# Adafruit_555_PWM_Output_STEMMA.net
KiCad netlist of a schematic drawn in EAGLE
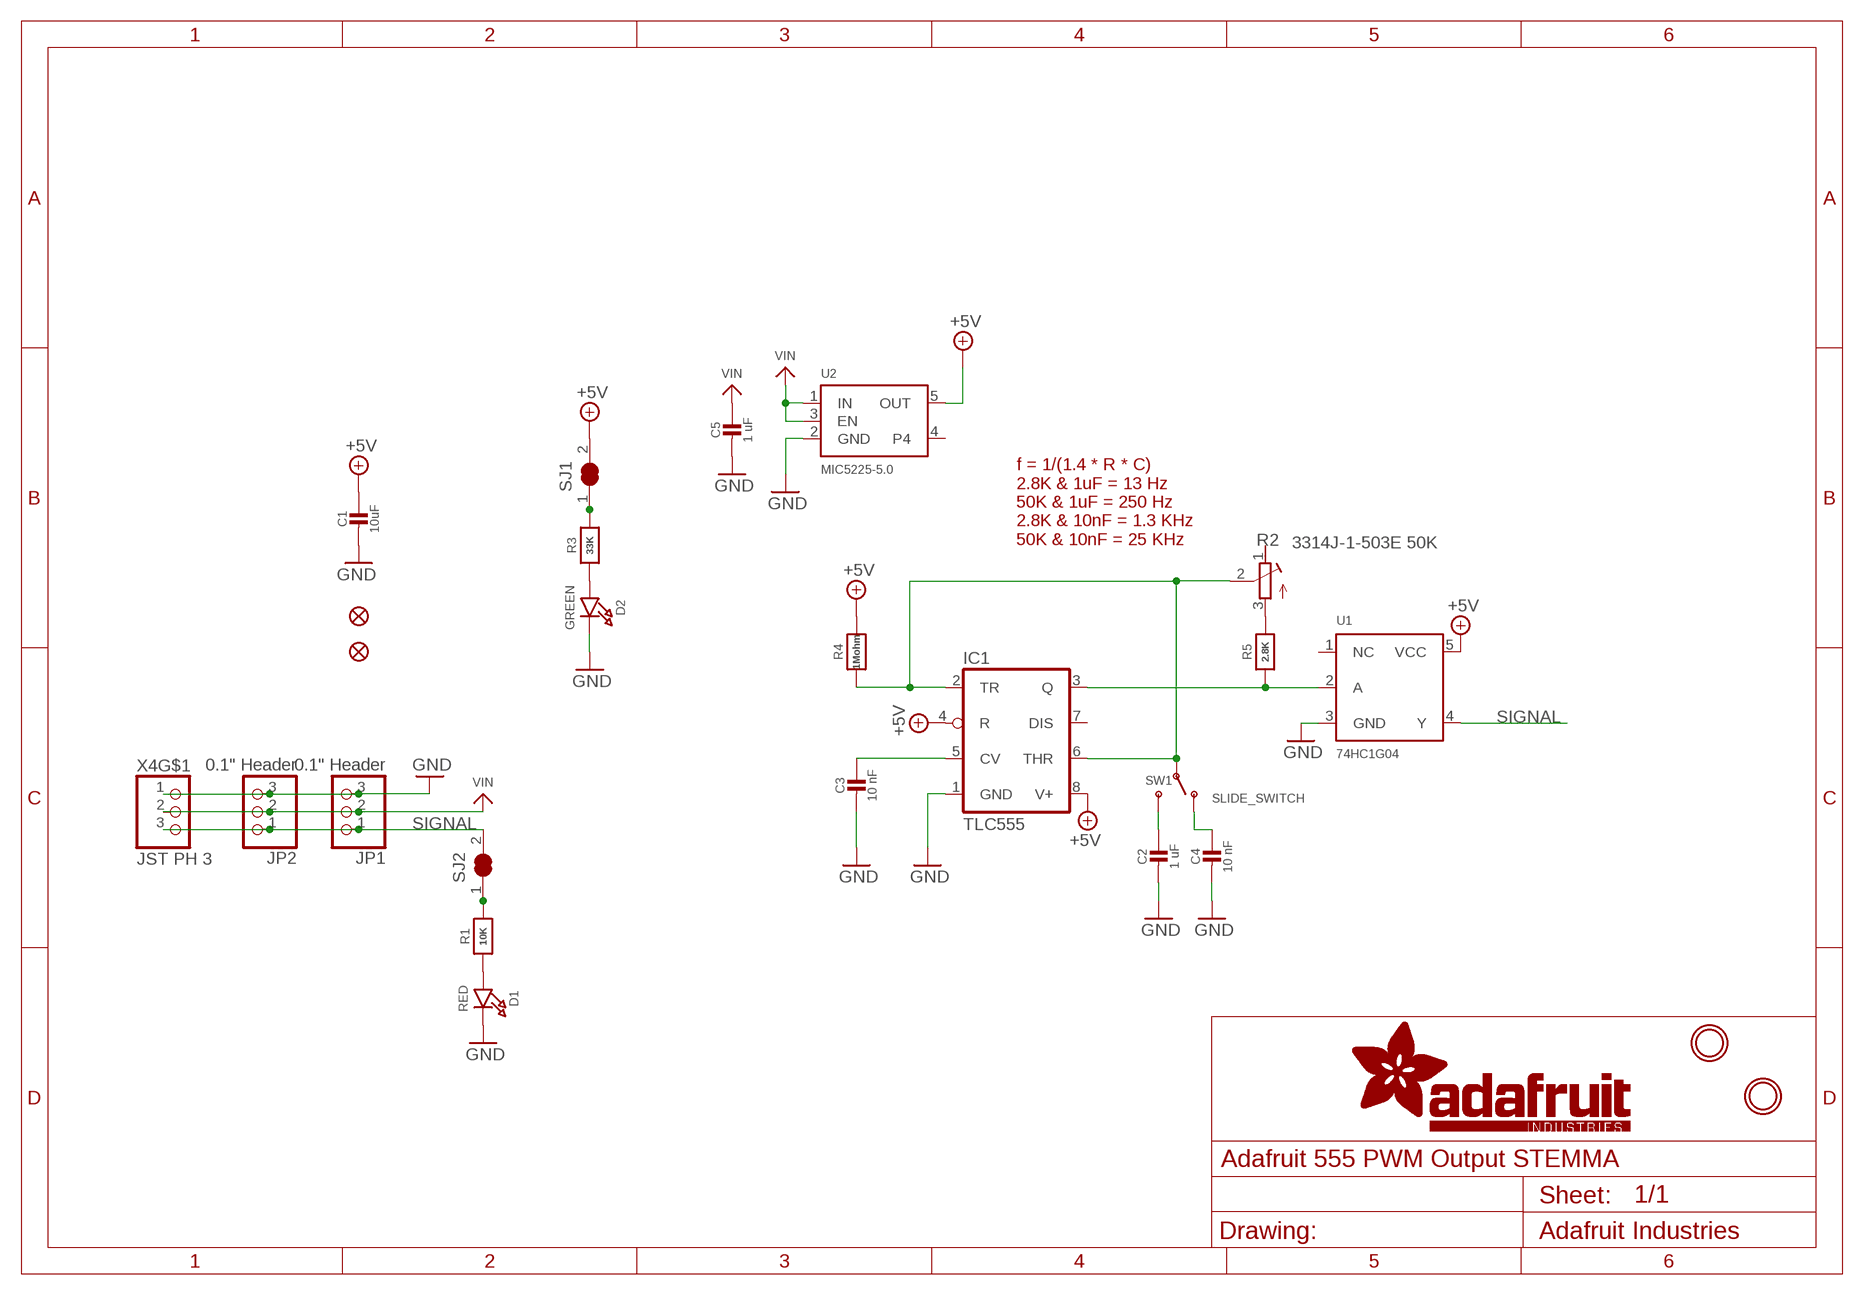
[diagram p0: schematic, sheet 1]

(export (version "E")
  (design (tool "Eeschema 10.0.6"))
  (components
    (comp (ref "C1")
      (value "10uF")
      (footprint "eagle-import:0805-NO")
      (libsource (lib "eagle-import") (part "CAP_CERAMIC0805-NOOUTLINE"))
    )
    (comp (ref "C2")
      (value "1 uF")
      (footprint "eagle-import:0603-NO")
      (libsource (lib "eagle-import") (part "CAP_CERAMIC0603_NO"))
    )
    (comp (ref "C3")
      (value "10 nF")
      (footprint "eagle-import:0603-NO")
      (libsource (lib "eagle-import") (part "CAP_CERAMIC0603_NO"))
    )
    (comp (ref "C4")
      (value "10 nF")
      (footprint "eagle-import:0603-NO")
      (libsource (lib "eagle-import") (part "CAP_CERAMIC0603_NO"))
    )
    (comp (ref "C5")
      (value "1 uF")
      (footprint "eagle-import:0603-NO")
      (libsource (lib "eagle-import") (part "CAP_CERAMIC0603_NO"))
    )
    (comp (ref "D1")
      (value "RED")
      (footprint "eagle-import:CHIPLED_0603_NOOUTLINE")
      (libsource (lib "eagle-import") (part "LED0603_NOOUTLINE"))
    )
    (comp (ref "D2")
      (value "GREEN")
      (footprint "eagle-import:CHIPLED_0603_NOOUTLINE")
      (libsource (lib "eagle-import") (part "LED0603_NOOUTLINE"))
    )
    (comp (ref "FID2")
      (value "FIDUCIAL_1MM")
      (footprint "eagle-import:FIDUCIAL_1MM")
      (libsource (lib "eagle-import") (part "FIDUCIAL_1MM"))
    )
    (comp (ref "FID3")
      (value "FIDUCIAL_1MM")
      (footprint "eagle-import:FIDUCIAL_1MM")
      (libsource (lib "eagle-import") (part "FIDUCIAL_1MM"))
    )
    (comp (ref "IC1")
      (value "TLC555")
      (footprint "eagle-import:SO08")
      (libsource (lib "eagle-import") (part "555DLM"))
    )
    (comp (ref "JP1")
      (value "0.1\" Header")
      (footprint "eagle-import:1X03_OVAL")
      (libsource (lib "eagle-import") (part "HEADER-1X3"))
    )
    (comp (ref "JP2")
      (value "0.1\" Header")
      (footprint "eagle-import:1X03_ROUND")
      (libsource (lib "eagle-import") (part "HEADER-1X3ROUND"))
    )
    (comp (ref "R1")
      (value "10K")
      (footprint "eagle-import:0603-NO")
      (libsource (lib "eagle-import") (part "RESISTOR_0603_NOOUT"))
    )
    (comp (ref "R2")
      (value "3314J-1-503E 50K")
      (footprint "eagle-import:RTRIM3314J")
      (libsource (lib "eagle-import") (part "R-TRIMM3314J"))
    )
    (comp (ref "R3")
      (value "33K")
      (footprint "eagle-import:0603-NO")
      (libsource (lib "eagle-import") (part "RESISTOR_0603_NOOUT"))
    )
    (comp (ref "R4")
      (value "1Mohm")
      (footprint "eagle-import:0603-NO")
      (libsource (lib "eagle-import") (part "RESISTOR_0603_NOOUT"))
    )
    (comp (ref "R5")
      (value "2.8K")
      (footprint "eagle-import:0603-NO")
      (libsource (lib "eagle-import") (part "RESISTOR_0603_NOOUT"))
    )
    (comp (ref "SJ1")
      (value "SOLDERJUMPER_CLOSED")
      (footprint "eagle-import:SOLDERJUMPER_CLOSEDWIRE")
      (libsource (lib "eagle-import") (part "SOLDERJUMPER_CLOSED"))
    )
    (comp (ref "SJ2")
      (value "SOLDERJUMPER_CLOSED")
      (footprint "eagle-import:SOLDERJUMPER_CLOSEDWIRE")
      (libsource (lib "eagle-import") (part "SOLDERJUMPER_CLOSED"))
    )
    (comp (ref "SW1")
      (value "SLIDE_SWITCH")
      (footprint "eagle-import:SPDT_SMT_SSSS811101")
      (libsource (lib "eagle-import") (part "SWITCH_SPDT"))
    )
    (comp (ref "U$1")
      (value "MOUNTINGHOLE2.5")
      (footprint "eagle-import:MOUNTINGHOLE_2.5_PLATED")
      (libsource (lib "eagle-import") (part "MOUNTINGHOLE2.5"))
    )
    (comp (ref "U$8")
      (value "MOUNTINGHOLE2.5")
      (footprint "eagle-import:MOUNTINGHOLE_2.5_PLATED")
      (libsource (lib "eagle-import") (part "MOUNTINGHOLE2.5"))
    )
    (comp (ref "U1")
      (value "74HC1G04")
      (footprint "eagle-import:SC70-5")
      (libsource (lib "eagle-import") (part "74LVC1G04SC-70"))
    )
    (comp (ref "U2")
      (value "MIC5225-5.0")
      (footprint "eagle-import:SOT23-5")
      (libsource (lib "eagle-import") (part "VREG_SOT23-5"))
    )
    (comp (ref "X4")
      (value "JST PH 3")
      (footprint "eagle-import:JSTPH3")
      (libsource (lib "eagle-import") (part "CON_JST_PH_3PIN"))
    )
  )
  (nets
    (net (code "1") (name "+5V") (class "Default")
      (node (ref "C1") (pin "1") (pinfunction "1_1") (pintype "passive"))
      (node (ref "IC1") (pin "4") (pinfunction "R_4") (pintype "input"))
      (node (ref "IC1") (pin "8") (pinfunction "V+_8") (pintype "power_in"))
      (node (ref "R4") (pin "2") (pinfunction "2_2") (pintype "passive"))
      (node (ref "SJ1") (pin "2") (pinfunction "2_2") (pintype "passive"))
      (node (ref "U1") (pin "5") (pinfunction "VCC_5") (pintype "power_in"))
      (node (ref "U2") (pin "5") (pinfunction "OUT_5") (pintype "power_in"))
    )
    (net (code "2") (name "/SIGNAL") (class "Default")
      (node (ref "JP1") (pin "1") (pinfunction "1_1") (pintype "passive"))
      (node (ref "JP2") (pin "1") (pinfunction "1_1") (pintype "passive"))
      (node (ref "SJ2") (pin "2") (pinfunction "2_2") (pintype "passive"))
      (node (ref "U1") (pin "4") (pinfunction "Y_4") (pintype "bidirectional"))
      (node (ref "X4") (pin "3") (pinfunction "3_3") (pintype "passive"))
    )
    (net (code "3") (name "GND") (class "Default")
      (node (ref "C1") (pin "2") (pinfunction "2_2") (pintype "passive"))
      (node (ref "C2") (pin "2") (pinfunction "2_2") (pintype "passive"))
      (node (ref "C3") (pin "2") (pinfunction "2_2") (pintype "passive"))
      (node (ref "C4") (pin "2") (pinfunction "2_2") (pintype "passive"))
      (node (ref "C5") (pin "2") (pinfunction "2_2") (pintype "passive"))
      (node (ref "D1") (pin "C") (pinfunction "C_C") (pintype "passive"))
      (node (ref "D2") (pin "C") (pinfunction "C_C") (pintype "passive"))
      (node (ref "IC1") (pin "1") (pinfunction "GND_1") (pintype "power_in"))
      (node (ref "JP1") (pin "3") (pinfunction "3_3") (pintype "passive"))
      (node (ref "JP2") (pin "3") (pinfunction "3_3") (pintype "passive"))
      (node (ref "U1") (pin "3") (pinfunction "GND_3") (pintype "power_in"))
      (node (ref "U2") (pin "2") (pinfunction "GND_2") (pintype "power_in"))
      (node (ref "X4") (pin "1") (pinfunction "1_1") (pintype "passive"))
    )
    (net (code "4") (name "Net-(D1-PadA)") (class "Default")
      (node (ref "D1") (pin "A") (pinfunction "A_A") (pintype "passive"))
      (node (ref "R1") (pin "1") (pinfunction "1_1") (pintype "passive"))
    )
    (net (code "5") (name "Net-(D2-PadA)") (class "Default")
      (node (ref "D2") (pin "A") (pinfunction "A_A") (pintype "passive"))
      (node (ref "R3") (pin "1") (pinfunction "1_1") (pintype "passive"))
    )
    (net (code "6") (name "Net-(IC1-CV)") (class "Default")
      (node (ref "C3") (pin "1") (pinfunction "1_1") (pintype "passive"))
      (node (ref "IC1") (pin "5") (pinfunction "CV_5") (pintype "input"))
    )
    (net (code "7") (name "Net-(IC1-Q)") (class "Default")
      (node (ref "IC1") (pin "3") (pinfunction "Q_3") (pintype "output"))
      (node (ref "R5") (pin "1") (pinfunction "1_1") (pintype "passive"))
      (node (ref "U1") (pin "2") (pinfunction "A_2") (pintype "bidirectional"))
    )
    (net (code "8") (name "Net-(IC1-THR)") (class "Default")
      (node (ref "IC1") (pin "2") (pinfunction "TR_2") (pintype "input"))
      (node (ref "IC1") (pin "6") (pinfunction "THR_6") (pintype "input"))
      (node (ref "R2") (pin "2") (pinfunction "S_2") (pintype "passive"))
      (node (ref "R4") (pin "1") (pinfunction "1_1") (pintype "passive"))
      (node (ref "SW1") (pin "B") (pinfunction "P_B") (pintype "passive"))
    )
    (net (code "9") (name "Net-(R1-Pad2)") (class "Default")
      (node (ref "R1") (pin "2") (pinfunction "2_2") (pintype "passive"))
      (node (ref "SJ2") (pin "1") (pinfunction "1_1") (pintype "passive"))
    )
    (net (code "10") (name "Net-(R2-A)") (class "Default")
      (node (ref "R2") (pin "3") (pinfunction "A_3") (pintype "passive"))
      (node (ref "R5") (pin "2") (pinfunction "2_2") (pintype "passive"))
    )
    (net (code "11") (name "Net-(R3-Pad2)") (class "Default")
      (node (ref "R3") (pin "2") (pinfunction "2_2") (pintype "passive"))
      (node (ref "SJ1") (pin "1") (pinfunction "1_1") (pintype "passive"))
    )
    (net (code "12") (name "Net-(SW1-O)") (class "Default")
      (node (ref "C4") (pin "1") (pinfunction "1_1") (pintype "passive"))
      (node (ref "SW1") (pin "A") (pinfunction "O_A") (pintype "passive"))
    )
    (net (code "13") (name "Net-(SW1-S)") (class "Default")
      (node (ref "C2") (pin "1") (pinfunction "1_1") (pintype "passive"))
      (node (ref "SW1") (pin "C") (pinfunction "S_C") (pintype "passive"))
    )
    (net (code "14") (name "VIN") (class "Default")
      (node (ref "C5") (pin "1") (pinfunction "1_1") (pintype "passive"))
      (node (ref "JP1") (pin "2") (pinfunction "2_2") (pintype "passive"))
      (node (ref "JP2") (pin "2") (pinfunction "2_2") (pintype "passive"))
      (node (ref "U2") (pin "1") (pinfunction "IN_1") (pintype "power_in"))
      (node (ref "U2") (pin "3") (pinfunction "EN_3") (pintype "input"))
      (node (ref "X4") (pin "2") (pinfunction "2_2") (pintype "passive"))
    )
    (net (code "15") (name "unconnected-(IC1-DIS-Pad7)") (class "Default")
      (node (ref "IC1") (pin "7") (pinfunction "DIS_7") (pintype "input"))
    )
    (net (code "16") (name "unconnected-(R2-E-Pad1)") (class "Default")
      (node (ref "R2") (pin "1") (pinfunction "E_1") (pintype "passive"))
    )
    (net (code "17") (name "unconnected-(U1-NC-Pad1)") (class "Default")
      (node (ref "U1") (pin "1") (pinfunction "NC_1") (pintype "no_connect"))
    )
    (net (code "18") (name "unconnected-(U2-P4-Pad4)") (class "Default")
      (node (ref "U2") (pin "4") (pinfunction "P4_4") (pintype "bidirectional"))
    )
  )
)
